# Top.net
KiCad netlist of a schematic drawn in Altium Designer
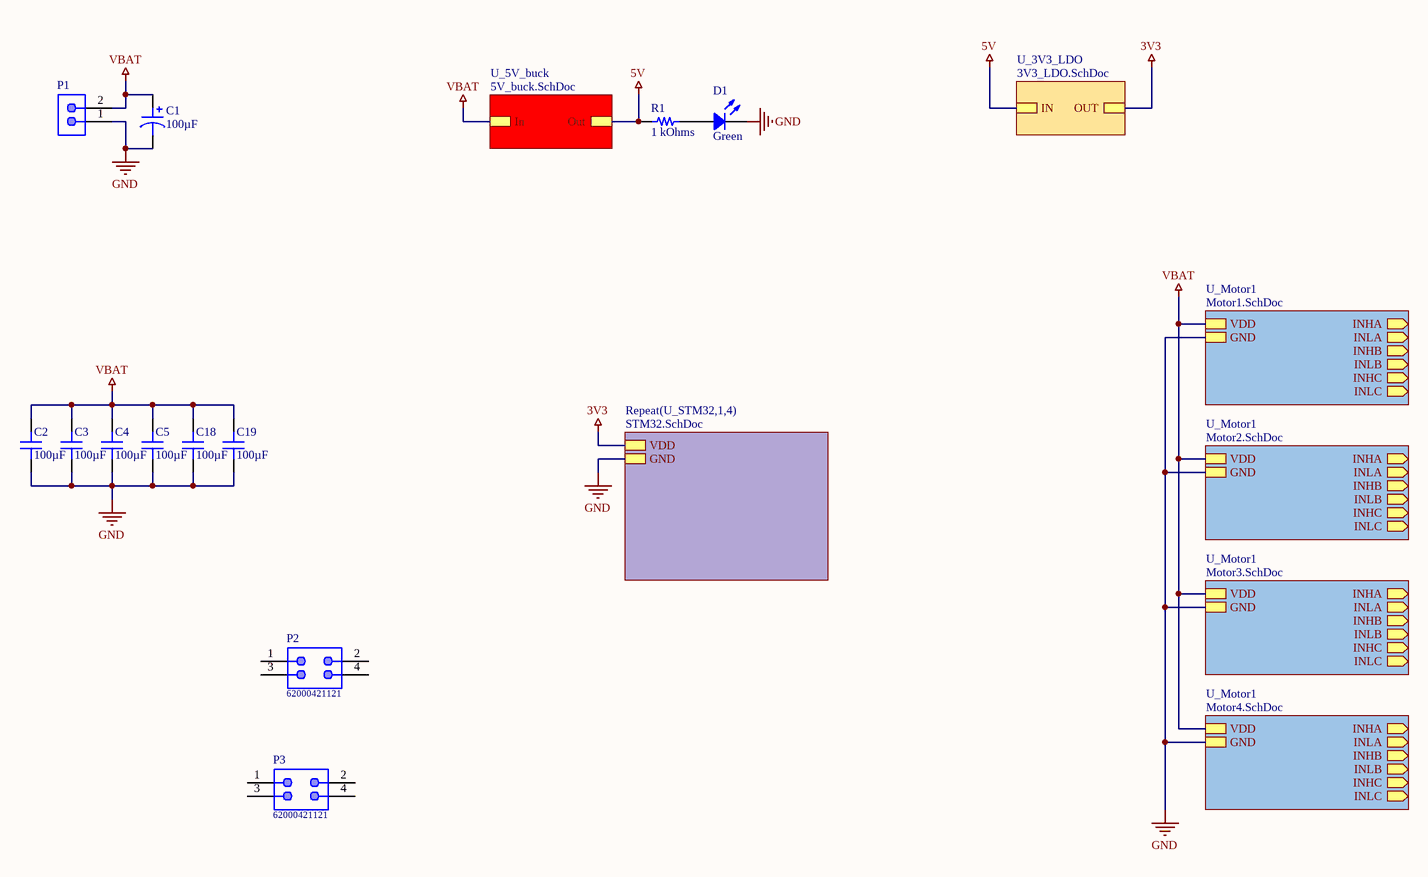
[diagram p0: Top.SchDoc]

(export (version "E")
  (design (tool "Eeschema 10.0.6"))
  (components
    (comp (ref "C1")
      (value "100µF")
      (footprint "CAP POL 2917_7343")
      (description "CAP TANT 100UF 20% 20V 2917")
      (fields (field (name "PART NUMBER") "293D107X0020E2TE3") (field (name "MANUFACTURER") "Vishay Sprague"))
      (libsource (lib "Celestial Altium Library - altium_library") (part "Polarised Capacitor"))
    )
    (comp (ref "C2")
      (value "100µF")
      (footprint "CAP 1210_3225 - 2.8MM")
      (description "CAP CER 100UF 6.3V X5R 1210")
      (fields (field (name "PART NUMBER") "12106D107MAT4A") (field (name "MANUFACTURER") "AVX Corporation"))
      (libsource (lib "Celestial Altium Library - altium_library") (part "Capacitor"))
    )
    (comp (ref "C3")
      (value "100µF")
      (footprint "CAP 1210_3225 - 2.8MM")
      (description "CAP CER 100UF 6.3V X5R 1210")
      (fields (field (name "PART NUMBER") "12106D107MAT4A") (field (name "MANUFACTURER") "AVX Corporation"))
      (libsource (lib "Celestial Altium Library - altium_library") (part "Capacitor"))
    )
    (comp (ref "C4")
      (value "100µF")
      (footprint "CAP 1210_3225 - 2.8MM")
      (description "CAP CER 100UF 6.3V X5R 1210")
      (fields (field (name "PART NUMBER") "12106D107MAT4A") (field (name "MANUFACTURER") "AVX Corporation"))
      (libsource (lib "Celestial Altium Library - altium_library") (part "Capacitor"))
    )
    (comp (ref "C5")
      (value "100µF")
      (footprint "CAP 1210_3225 - 2.8MM")
      (description "CAP CER 100UF 6.3V X5R 1210")
      (fields (field (name "PART NUMBER") "12106D107MAT4A") (field (name "MANUFACTURER") "AVX Corporation"))
      (libsource (lib "Celestial Altium Library - altium_library") (part "Capacitor"))
    )
    (comp (ref "C18")
      (value "100µF")
      (footprint "CAP 1210_3225 - 2.8MM")
      (description "CAP CER 100UF 6.3V X5R 1210")
      (fields (field (name "PART NUMBER") "12106D107MAT4A") (field (name "MANUFACTURER") "AVX Corporation"))
      (libsource (lib "Celestial Altium Library - altium_library") (part "Capacitor"))
    )
    (comp (ref "C19")
      (value "100µF")
      (footprint "CAP 1210_3225 - 2.8MM")
      (description "CAP CER 100UF 6.3V X5R 1210")
      (fields (field (name "PART NUMBER") "12106D107MAT4A") (field (name "MANUFACTURER") "AVX Corporation"))
      (libsource (lib "Celestial Altium Library - altium_library") (part "Capacitor"))
    )
    (comp (ref "D1")
      (value "Green")
      (footprint "LED 0603_1608 GREEN")
      (description "1.6X0.8MM LC GREEN PIXSOLED DOME")
      (fields (field (name "PART NUMBER") "XZCDGK53W-8VF") (field (name "MANUFACTURER") "SunLED"))
      (libsource (lib "Celestial Altium Library - altium_library") (part "LED"))
    )
    (comp (ref "P1")
      (value "2 pin 2mm JST Male")
      (footprint "2pin - 2mm JST male")
      (libsource (lib "IC") (part "2 pin 2mm JST Male"))
    )
    (comp (ref "P2")
      (value "62000421121")
      (footprint "62000421121")
      (description "WR-PHD Pin Header, THT, pitch 2mm, Dual Row, Vertical, 4p")
      (fields (field (name "MANUFACTURER") "Wurth Elektronik"))
      (libsource (lib "Altium_WR-PHD") (part "62000421121"))
    )
    (comp (ref "P3")
      (value "62000421121")
      (footprint "62000421121")
      (description "WR-PHD Pin Header, THT, pitch 2mm, Dual Row, Vertical, 4p")
      (fields (field (name "MANUFACTURER") "Wurth Elektronik"))
      (libsource (lib "Altium_WR-PHD") (part "62000421121"))
    )
    (comp (ref "R1")
      (value "1 kOhms")
      (footprint "RES 0603_1608")
      (description "RES 1K OHM 0.5% 1/10W 0603")
      (fields
        (field (name "PART NUMBER") "RNCF0603DTE1K00")
        (field (name "MANUFACTURER") "Stackpole Electronics Inc")
      )
      (libsource (lib "Celestial Altium Library - altium_library") (part "Resistor"))
    )
  )
  (nets
    (net (code "26") (name "5V") (class "Default")
      (node (ref "R1") (pin "1") (pinfunction "1_1") (pintype "passive"))
    )
    (net (code "27") (name "GND") (class "Default")
      (node (ref "C1") (pin "2") (pinfunction "2_2") (pintype "passive"))
      (node (ref "C18") (pin "1") (pinfunction "1_1") (pintype "passive"))
      (node (ref "C19") (pin "1") (pinfunction "1_1") (pintype "passive"))
      (node (ref "C2") (pin "1") (pinfunction "1_1") (pintype "passive"))
      (node (ref "C3") (pin "1") (pinfunction "1_1") (pintype "passive"))
      (node (ref "C4") (pin "1") (pinfunction "1_1") (pintype "passive"))
      (node (ref "C5") (pin "1") (pinfunction "1_1") (pintype "passive"))
      (node (ref "D1") (pin "2") (pinfunction "2_2") (pintype "passive"))
      (node (ref "P1") (pin "1") (pinfunction "1_1") (pintype "passive"))
    )
    (net (code "28") (name "Net-(D1-Pad1)") (class "Default")
      (node (ref "D1") (pin "1") (pinfunction "1_1") (pintype "passive"))
      (node (ref "R1") (pin "2") (pinfunction "2_2") (pintype "passive"))
    )
    (net (code "29") (name "VBAT") (class "Default")
      (node (ref "C1") (pin "1") (pinfunction "1_1") (pintype "passive"))
      (node (ref "C18") (pin "2") (pinfunction "2_2") (pintype "passive"))
      (node (ref "C19") (pin "2") (pinfunction "2_2") (pintype "passive"))
      (node (ref "C2") (pin "2") (pinfunction "2_2") (pintype "passive"))
      (node (ref "C3") (pin "2") (pinfunction "2_2") (pintype "passive"))
      (node (ref "C4") (pin "2") (pinfunction "2_2") (pintype "passive"))
      (node (ref "C5") (pin "2") (pinfunction "2_2") (pintype "passive"))
      (node (ref "P1") (pin "2") (pinfunction "2_2") (pintype "passive"))
    )
    (net (code "30") (name "unconnected-(P2-Pad1)") (class "Default")
      (node (ref "P2") (pin "1") (pinfunction "1_1") (pintype "passive"))
    )
    (net (code "31") (name "unconnected-(P2-Pad2)") (class "Default")
      (node (ref "P2") (pin "2") (pinfunction "2_2") (pintype "passive"))
    )
    (net (code "32") (name "unconnected-(P2-Pad3)") (class "Default")
      (node (ref "P2") (pin "3") (pinfunction "3_3") (pintype "passive"))
    )
    (net (code "33") (name "unconnected-(P2-Pad4)") (class "Default")
      (node (ref "P2") (pin "4") (pinfunction "4_4") (pintype "passive"))
    )
    (net (code "34") (name "unconnected-(P3-Pad1)") (class "Default")
      (node (ref "P3") (pin "1") (pinfunction "1_1") (pintype "passive"))
    )
    (net (code "35") (name "unconnected-(P3-Pad2)") (class "Default")
      (node (ref "P3") (pin "2") (pinfunction "2_2") (pintype "passive"))
    )
    (net (code "36") (name "unconnected-(P3-Pad3)") (class "Default")
      (node (ref "P3") (pin "3") (pinfunction "3_3") (pintype "passive"))
    )
    (net (code "37") (name "unconnected-(P3-Pad4)") (class "Default")
      (node (ref "P3") (pin "4") (pinfunction "4_4") (pintype "passive"))
    )
  )
)
